# walter.net
KiCad netlist of a schematic drawn in EAGLE
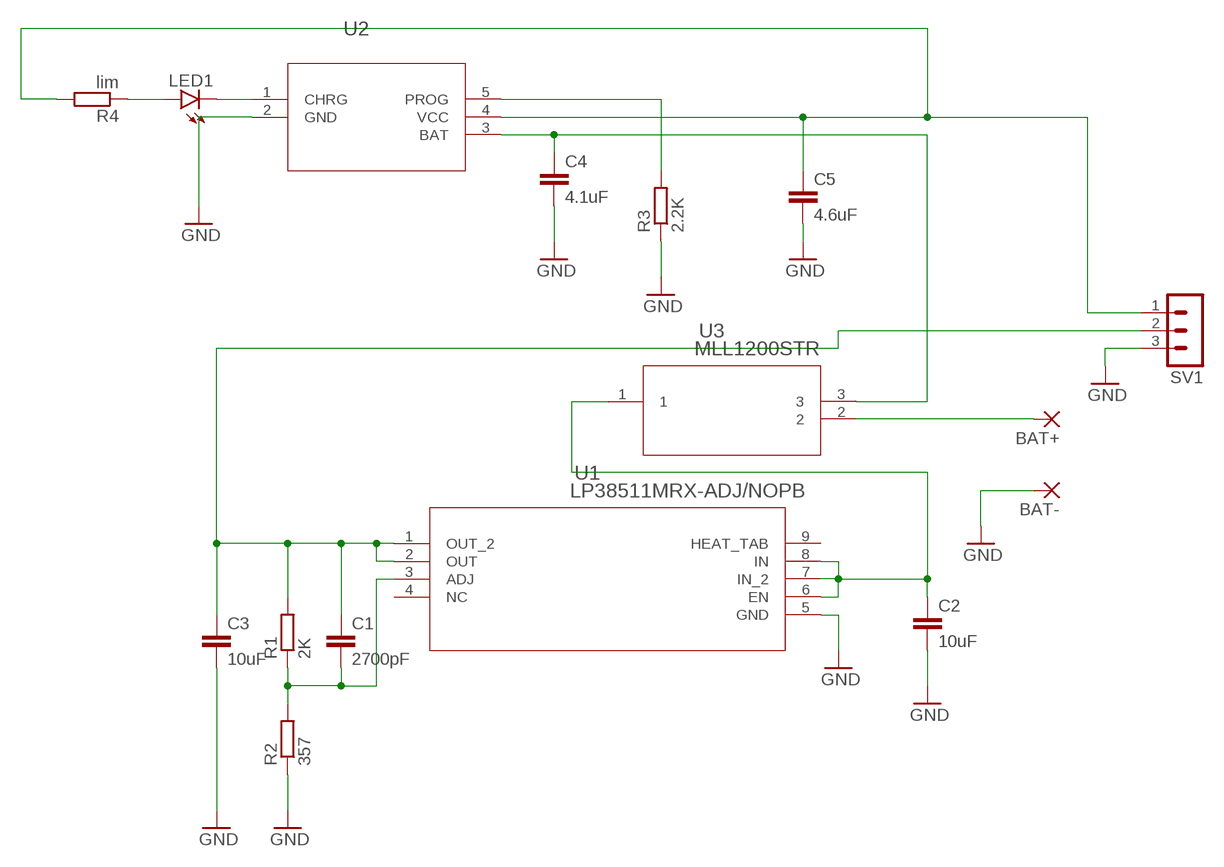
[diagram p0: schematic, sheet 1]

(export (version "E")
  (design (tool "Eeschema 10.0.6"))
  (components
    (comp (ref "BAT+")
      (value "1,6/0,8")
      (footprint "eagle-import:1,6_0,8")
      (libsource (lib "eagle-import") (part "1,6/0,8"))
    )
    (comp (ref "BAT-")
      (value "1,6/0,8")
      (footprint "eagle-import:1,6_0,8")
      (libsource (lib "eagle-import") (part "1,6/0,8"))
    )
    (comp (ref "C1")
      (value "2700pF")
      (footprint "eagle-import:C0402")
      (libsource (lib "eagle-import") (part "C-EUC0402"))
    )
    (comp (ref "C2")
      (value "10uF")
      (footprint "eagle-import:C0603")
      (libsource (lib "eagle-import") (part "C-EUC0603"))
    )
    (comp (ref "C3")
      (value "10uF")
      (footprint "eagle-import:C0603")
      (libsource (lib "eagle-import") (part "C-EUC0603"))
    )
    (comp (ref "C4")
      (value "4.1uF")
      (footprint "eagle-import:C0603")
      (libsource (lib "eagle-import") (part "C-EUC0603"))
    )
    (comp (ref "C5")
      (value "4.6uF")
      (footprint "eagle-import:C0603")
      (libsource (lib "eagle-import") (part "C-EUC0603"))
    )
    (comp (ref "LED1")
      (value "LEDCHIP-LED0603")
      (footprint "eagle-import:CHIP-LED0603")
      (libsource (lib "eagle-import") (part "LEDCHIP-LED0603"))
    )
    (comp (ref "R1")
      (value "2K")
      (footprint "eagle-import:R0402")
      (libsource (lib "eagle-import") (part "R-EU_R0402"))
    )
    (comp (ref "R2")
      (value "357")
      (footprint "eagle-import:R0603")
      (libsource (lib "eagle-import") (part "R-EU_R0603"))
    )
    (comp (ref "R3")
      (value "2.2K")
      (footprint "eagle-import:R0603")
      (libsource (lib "eagle-import") (part "R-EU_R0603"))
    )
    (comp (ref "R4")
      (value "lim")
      (footprint "eagle-import:R0402")
      (libsource (lib "eagle-import") (part "R-EU_R0402"))
    )
    (comp (ref "SV1")
      (value "MA03-1")
      (footprint "eagle-import:MA03-1")
      (libsource (lib "eagle-import") (part "MA03-1"))
    )
    (comp (ref "U1")
      (value "LP38511MRX-ADJ/NOPB")
      (footprint "eagle-import:MRA08B_TEX")
      (libsource (lib "eagle-import") (part "LP38511MRX-ADJ/NOPB"))
    )
    (comp (ref "U2")
      (value "LTC4054LES5-4.2TRPBF")
      (footprint "eagle-import:S_5_ADI")
      (fields
        (field (name "MANUFACTURER_PART_NUMBER") "LTC4054LES5-4.2#TRPBF")
        (field (name "COPYRIGHT") "Copyright (C) 2016 Accelerated Designs. All rights reserved")
      )
      (libsource (lib "eagle-import") (part "LTC4054LES5-4.2TRPBF"))
    )
    (comp (ref "U3")
      (value "MLL1200STR")
      (footprint "eagle-import:SW_MLL1200STR_TEC")
      (fields (field (name "COPYRIGHT") "Copyright (C) 2018 Accelerated Designs. All rights reserved"))
      (libsource (lib "eagle-import") (part "MLL1200STR"))
    )
  )
  (nets
    (net (code "1") (name "GND") (class "Default")
      (node (ref "BAT-") (pin "1") (pinfunction "P_1") (pintype "passive"))
      (node (ref "C2") (pin "2") (pinfunction "2_2") (pintype "passive"))
      (node (ref "C3") (pin "2") (pinfunction "2_2") (pintype "passive"))
      (node (ref "C4") (pin "2") (pinfunction "2_2") (pintype "passive"))
      (node (ref "C5") (pin "2") (pinfunction "2_2") (pintype "passive"))
      (node (ref "R2") (pin "1") (pinfunction "1_1") (pintype "passive"))
      (node (ref "R3") (pin "1") (pinfunction "1_1") (pintype "passive"))
      (node (ref "SV1") (pin "3") (pinfunction "3_3") (pintype "passive"))
      (node (ref "U1") (pin "5") (pinfunction "GND_5") (pintype "power_in"))
      (node (ref "U2") (pin "2") (pinfunction "GND_2") (pintype "passive"))
    )
    (net (code "2") (name "Net-(BAT+-P)") (class "Default")
      (node (ref "BAT+") (pin "1") (pinfunction "P_1") (pintype "passive"))
      (node (ref "U3") (pin "2") (pinfunction "2_2") (pintype "passive"))
    )
    (net (code "3") (name "Net-(LED1-PadA)") (class "Default")
      (node (ref "LED1") (pin "A") (pinfunction "A_A") (pintype "passive"))
      (node (ref "R4") (pin "1") (pinfunction "1_1") (pintype "passive"))
    )
    (net (code "4") (name "Net-(U1-ADJ)") (class "Default")
      (node (ref "C1") (pin "2") (pinfunction "2_2") (pintype "passive"))
      (node (ref "R1") (pin "1") (pinfunction "1_1") (pintype "passive"))
      (node (ref "R2") (pin "2") (pinfunction "2_2") (pintype "passive"))
      (node (ref "U1") (pin "3") (pinfunction "ADJ_3") (pintype "passive"))
    )
    (net (code "5") (name "Net-(U1-EN)") (class "Default")
      (node (ref "C2") (pin "1") (pinfunction "1_1") (pintype "passive"))
      (node (ref "U1") (pin "6") (pinfunction "EN_6") (pintype "input"))
      (node (ref "U1") (pin "7") (pinfunction "IN_2_7") (pintype "input"))
      (node (ref "U1") (pin "8") (pinfunction "IN_8") (pintype "input"))
      (node (ref "U3") (pin "1") (pinfunction "1_1") (pintype "passive"))
    )
    (net (code "6") (name "Net-(U1-OUT)") (class "Default")
      (node (ref "C1") (pin "1") (pinfunction "1_1") (pintype "passive"))
      (node (ref "C3") (pin "1") (pinfunction "1_1") (pintype "passive"))
      (node (ref "R1") (pin "2") (pinfunction "2_2") (pintype "passive"))
      (node (ref "SV1") (pin "2") (pinfunction "2_2") (pintype "passive"))
      (node (ref "U1") (pin "1") (pinfunction "OUT_2_1") (pintype "output"))
      (node (ref "U1") (pin "2") (pinfunction "OUT_2") (pintype "output"))
    )
    (net (code "7") (name "Net-(U2-BAT)") (class "Default")
      (node (ref "C4") (pin "1") (pinfunction "1_1") (pintype "passive"))
      (node (ref "U2") (pin "3") (pinfunction "BAT_3") (pintype "passive"))
      (node (ref "U3") (pin "3") (pinfunction "3_3") (pintype "passive"))
    )
    (net (code "8") (name "Net-(U2-CHRG)") (class "Default")
      (node (ref "LED1") (pin "C") (pinfunction "C_C") (pintype "passive"))
      (node (ref "U2") (pin "1") (pinfunction "CHRG_1") (pintype "passive"))
    )
    (net (code "9") (name "Net-(U2-PROG)") (class "Default")
      (node (ref "R3") (pin "2") (pinfunction "2_2") (pintype "passive"))
      (node (ref "U2") (pin "5") (pinfunction "PROG_5") (pintype "passive"))
    )
    (net (code "10") (name "Net-(U2-VCC)") (class "Default")
      (node (ref "C5") (pin "1") (pinfunction "1_1") (pintype "passive"))
      (node (ref "R4") (pin "2") (pinfunction "2_2") (pintype "passive"))
      (node (ref "SV1") (pin "1") (pinfunction "1_1") (pintype "passive"))
      (node (ref "U2") (pin "4") (pinfunction "VCC_4") (pintype "power_in"))
    )
    (net (code "11") (name "unconnected-(U1-HEAT_TAB-Pad9)") (class "Default")
      (node (ref "U1") (pin "9") (pinfunction "HEAT_TAB_9") (pintype "passive"))
    )
    (net (code "12") (name "unconnected-(U1-NC-Pad4)") (class "Default")
      (node (ref "U1") (pin "4") (pinfunction "NC_4") (pintype "no_connect"))
    )
  )
)
